# ESP8285.net
KiCad netlist of a schematic drawn in Altium Designer
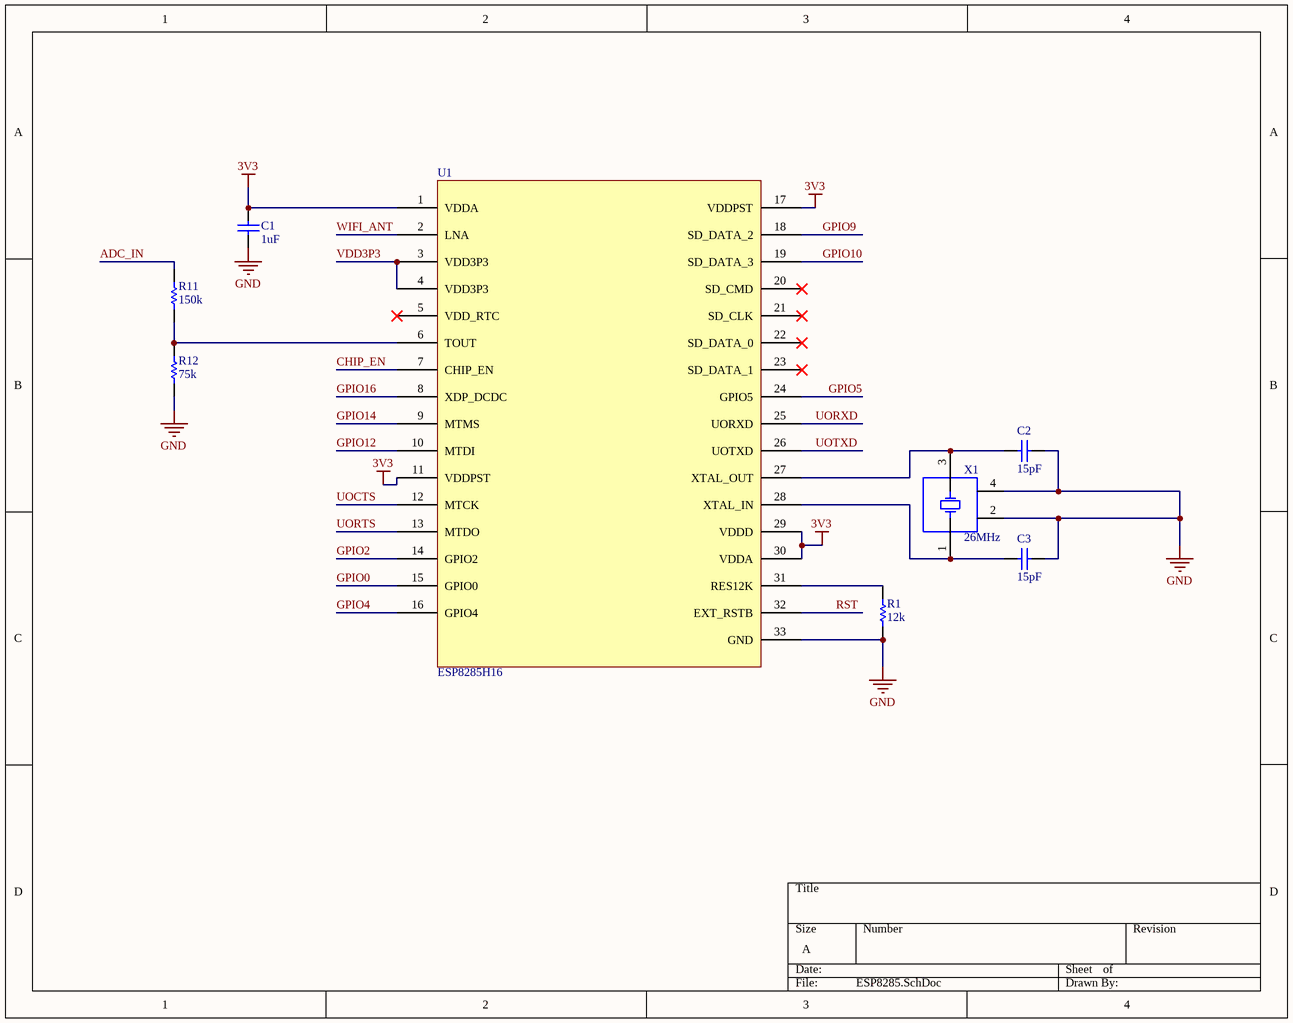
[diagram p0: ESP8285.SchDoc]

(export (version "E")
  (design (tool "Eeschema 10.0.6"))
  (components
    (comp (ref "C1")
      (value "1uF")
      (footprint "C0805")
      (description "0805 1 uF 25 V ±10 % Tolerance X7R SMT Multilayer Ceramic Capacitor")
      (fields (field (name "MANUFACTURER PART NUMBER") "CC0805KKX7R8BB105"))
      (libsource (lib "CommunityVault") (part "CAP-NP-2"))
    )
    (comp (ref "C2")
      (value "15pF")
      (footprint "PCB-98fz84kwkqgd8opjlb99-1")
      (fields
        (field (name "MANUFACTURER PART NUMBER") "GRM1555C1H150FA01D")
        (field (name "TOLERANCE") "±1%")
        (field (name "MANUFACTURER") "Murata Electronics North America")
      )
      (libsource (lib "CommunityVault") (part "SYM-a0ab688c22207f6c-1"))
    )
    (comp (ref "C3")
      (value "15pF")
      (footprint "PCB-98fz84kwkqgd8opjlb99-1")
      (fields
        (field (name "MANUFACTURER PART NUMBER") "GRM1555C1H150FA01D")
        (field (name "TOLERANCE") "±1%")
        (field (name "MANUFACTURER") "Murata Electronics North America")
      )
      (libsource (lib "CommunityVault") (part "SYM-a0ab688c22207f6c-1"))
    )
    (comp (ref "R1")
      (value "12k")
      (footprint "RESC1609X50X30LL10T20")
      (description "Res Thick Film 0603 12K Ohm 1% 0.1W(1/10W) ±100ppm/C Molded SMD Automotive Paper T/R")
      (libsource (lib "CommunityVault") (part "SYM-76f8bd925226a93f-1"))
    )
    (comp (ref "R11")
      (value "150k")
      (footprint "RESC1608X55X30LL15T15")
      (description "Thick Film Resistors - SMD 0603 150Kohms 1% Tol")
      (fields (field (name "MANUFACTURER PART NUMBER") "ERJ-3EKF1503V"))
      (libsource (lib "CommunityVault") (part "RES-2"))
    )
    (comp (ref "R12")
      (value "75k")
      (footprint "RESC1608X55X30LL15T15")
      (description "Thick Film Resistors - SMD 0603 75Kohms 1% Tol")
      (fields (field (name "MANUFACTURER PART NUMBER") "ERJ-3EKF7502V"))
      (libsource (lib "CommunityVault") (part "RES-2"))
    )
    (comp (ref "U1")
      (value "ESP8285H16")
      (footprint "PCB-1fh2hqe1x48mh17li7t6-1")
      (description "RF Transceiver 64QAM/BPSK/CCK/DSSS/OFDM 2.7V to 3.6V 2400MHz to 2483.5MHz 32-Pin QFN")
      (libsource (lib "FavoritesLibrary") (part "SYM-265ae9019d32f99d-1"))
    )
    (comp (ref "X1")
      (value "26MHz")
      (footprint "PCB-1zhjv6m1p58g6yr6i7sc-1")
      (description "Crystal 26MHz ±10ppm (Tol) ±10ppm (Stability) 10pF FUND 50Ohm 4-Pin CSMD T/R")
      (fields (field (name "MANUFACTURER PART NUMBER") "ABM8-26.000MHZ-10-1-U-T"))
      (libsource (lib "CommunityVault") (part "SYM-932d5a23796e4cea-1"))
    )
  )
  (nets
    (net (code "1") (name "/ADC_IN") (class "Default")
      (node (ref "R11") (pin "2") (pinfunction "2_2") (pintype "passive"))
    )
    (net (code "2") (name "/CHIP_EN") (class "Default")
      (node (ref "U1") (pin "7") (pinfunction "CHIP_EN_7") (pintype "passive"))
    )
    (net (code "3") (name "/GPIO0") (class "Default")
      (node (ref "U1") (pin "15") (pinfunction "GPIO0_15") (pintype "passive"))
    )
    (net (code "4") (name "/GPIO2") (class "Default")
      (node (ref "U1") (pin "14") (pinfunction "GPIO2_14") (pintype "passive"))
    )
    (net (code "5") (name "/GPIO4") (class "Default")
      (node (ref "U1") (pin "16") (pinfunction "GPIO4_16") (pintype "passive"))
    )
    (net (code "6") (name "/GPIO5") (class "Default")
      (node (ref "U1") (pin "24") (pinfunction "GPIO5_24") (pintype "passive"))
    )
    (net (code "7") (name "/GPIO9") (class "Default")
      (node (ref "U1") (pin "18") (pinfunction "SD_DATA_2_18") (pintype "passive"))
    )
    (net (code "8") (name "/GPIO10") (class "Default")
      (node (ref "U1") (pin "19") (pinfunction "SD_DATA_3_19") (pintype "passive"))
    )
    (net (code "9") (name "/GPIO12") (class "Default")
      (node (ref "U1") (pin "10") (pinfunction "MTDI_10") (pintype "passive"))
    )
    (net (code "10") (name "/GPIO14") (class "Default")
      (node (ref "U1") (pin "9") (pinfunction "MTMS_9") (pintype "passive"))
    )
    (net (code "11") (name "/GPIO16") (class "Default")
      (node (ref "U1") (pin "8") (pinfunction "XDP_DCDC_8") (pintype "passive"))
    )
    (net (code "12") (name "/RST") (class "Default")
      (node (ref "U1") (pin "32") (pinfunction "EXT_RSTB_32") (pintype "passive"))
    )
    (net (code "13") (name "/UOCTS") (class "Default")
      (node (ref "U1") (pin "12") (pinfunction "MTCK_12") (pintype "passive"))
    )
    (net (code "14") (name "/UORTS") (class "Default")
      (node (ref "U1") (pin "13") (pinfunction "MTDO_13") (pintype "passive"))
    )
    (net (code "15") (name "/UORXD") (class "Default")
      (node (ref "U1") (pin "25") (pinfunction "UORXD_25") (pintype "passive"))
    )
    (net (code "16") (name "/UOTXD") (class "Default")
      (node (ref "U1") (pin "26") (pinfunction "UOTXD_26") (pintype "passive"))
    )
    (net (code "17") (name "/VDD3P3") (class "Default")
      (node (ref "U1") (pin "3") (pinfunction "VDD3P3_3") (pintype "power_in"))
      (node (ref "U1") (pin "4") (pinfunction "VDD3P3_4") (pintype "power_in"))
    )
    (net (code "18") (name "/WIFI_ANT") (class "Default")
      (node (ref "U1") (pin "2") (pinfunction "LNA_2") (pintype "passive"))
    )
    (net (code "19") (name "3V3") (class "Default")
      (node (ref "C1") (pin "1") (pinfunction "1_1") (pintype "passive"))
      (node (ref "U1") (pin "1") (pinfunction "VDDA_1") (pintype "power_in"))
      (node (ref "U1") (pin "11") (pinfunction "VDDPST_11") (pintype "passive"))
      (node (ref "U1") (pin "17") (pinfunction "VDDPST_17") (pintype "passive"))
      (node (ref "U1") (pin "29") (pinfunction "VDDD_29") (pintype "passive"))
      (node (ref "U1") (pin "30") (pinfunction "VDDA_30") (pintype "passive"))
    )
    (net (code "20") (name "GND") (class "Default")
      (node (ref "C1") (pin "2") (pinfunction "2_2") (pintype "passive"))
      (node (ref "C2") (pin "2") (pinfunction "2_2") (pintype "passive"))
      (node (ref "C3") (pin "2") (pinfunction "2_2") (pintype "passive"))
      (node (ref "R1") (pin "1") (pinfunction "1_1") (pintype "passive"))
      (node (ref "R12") (pin "1") (pinfunction "1_1") (pintype "passive"))
      (node (ref "U1") (pin "33") (pinfunction "GND_33") (pintype "passive"))
      (node (ref "X1") (pin "2") (pinfunction "2_2") (pintype "passive"))
      (node (ref "X1") (pin "4") (pinfunction "4_4") (pintype "passive"))
    )
    (net (code "21") (name "Net-(U1-RES12K)") (class "Default")
      (node (ref "R1") (pin "2") (pinfunction "2_2") (pintype "passive"))
      (node (ref "U1") (pin "31") (pinfunction "RES12K_31") (pintype "passive"))
    )
    (net (code "22") (name "Net-(U1-TOUT)") (class "Default")
      (node (ref "R11") (pin "1") (pinfunction "1_1") (pintype "passive"))
      (node (ref "R12") (pin "2") (pinfunction "2_2") (pintype "passive"))
      (node (ref "U1") (pin "6") (pinfunction "TOUT_6") (pintype "passive"))
    )
    (net (code "23") (name "Net-(U1-XTAL_IN)") (class "Default")
      (node (ref "C3") (pin "1") (pinfunction "1_1") (pintype "passive"))
      (node (ref "U1") (pin "28") (pinfunction "XTAL_IN_28") (pintype "passive"))
      (node (ref "X1") (pin "1") (pinfunction "1_1") (pintype "passive"))
    )
    (net (code "24") (name "Net-(U1-XTAL_OUT)") (class "Default")
      (node (ref "C2") (pin "1") (pinfunction "1_1") (pintype "passive"))
      (node (ref "U1") (pin "27") (pinfunction "XTAL_OUT_27") (pintype "passive"))
      (node (ref "X1") (pin "3") (pinfunction "3_3") (pintype "passive"))
    )
    (net (code "25") (name "unconnected-(U1-SD_CLK-Pad21)") (class "Default")
      (node (ref "U1") (pin "21") (pinfunction "SD_CLK_21") (pintype "passive+no_connect"))
    )
    (net (code "26") (name "unconnected-(U1-SD_CMD-Pad20)") (class "Default")
      (node (ref "U1") (pin "20") (pinfunction "SD_CMD_20") (pintype "passive+no_connect"))
    )
    (net (code "27") (name "unconnected-(U1-SD_DATA_0-Pad22)") (class "Default")
      (node (ref "U1") (pin "22") (pinfunction "SD_DATA_0_22") (pintype "passive+no_connect"))
    )
    (net (code "28") (name "unconnected-(U1-SD_DATA_1-Pad23)") (class "Default")
      (node (ref "U1") (pin "23") (pinfunction "SD_DATA_1_23") (pintype "passive+no_connect"))
    )
    (net (code "29") (name "unconnected-(U1-VDD_RTC-Pad5)") (class "Default")
      (node (ref "U1") (pin "5") (pinfunction "VDD_RTC_5") (pintype "passive+no_connect"))
    )
  )
)
